# SHT_7_I_Calibration_07349-R5_L10.net
KiCad netlist of a schematic drawn in Altium Designer
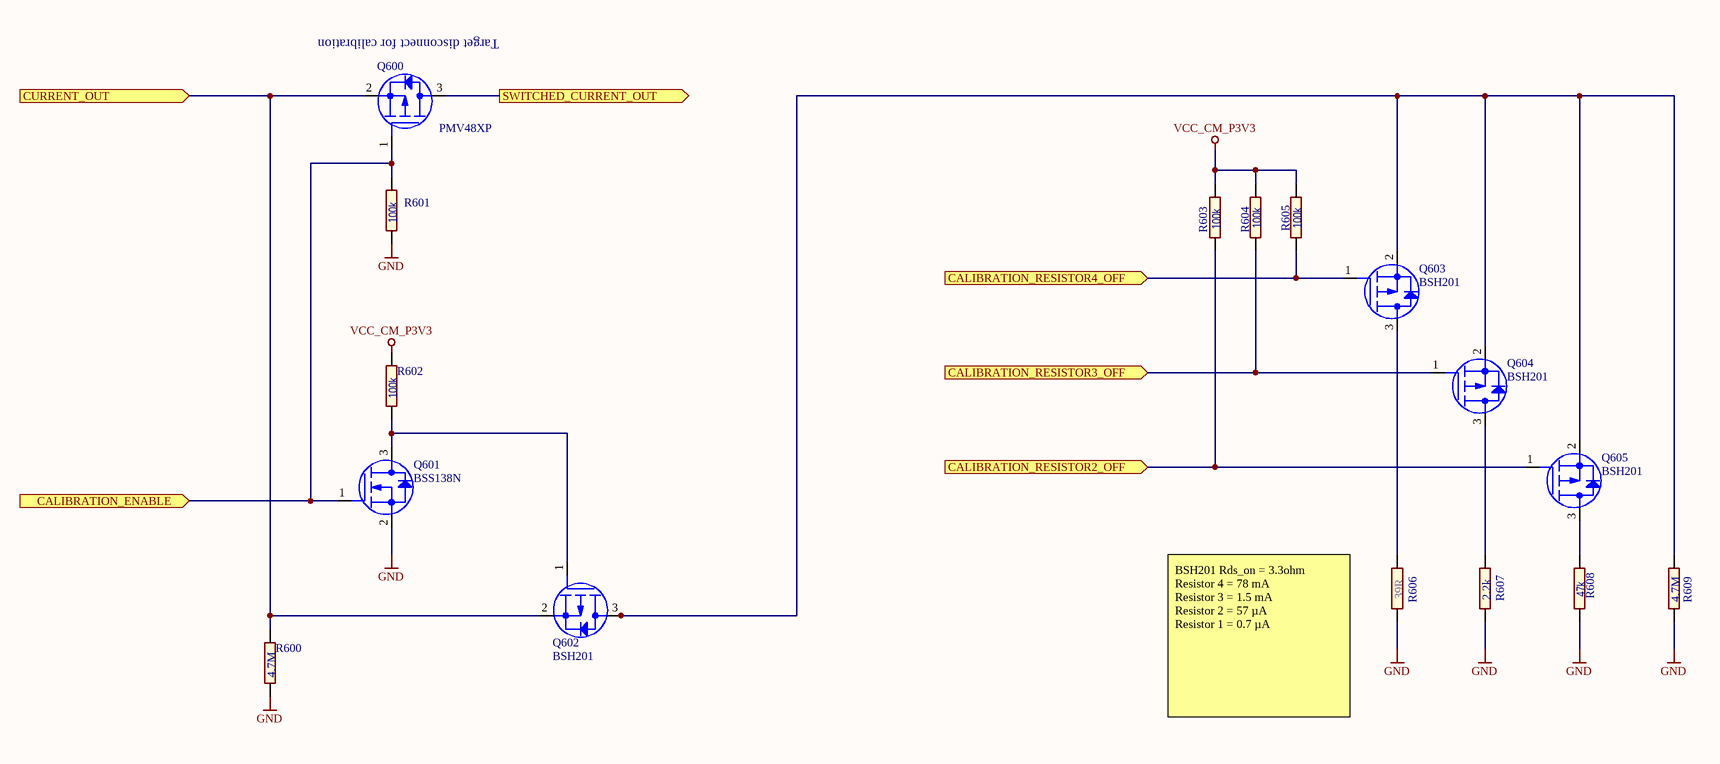
[diagram p0: SHT_7_I_Calibration_07349-R5_L10.SchDoc]

(export (version "E")
  (design (tool "Eeschema 10.0.6"))
  (components
    (comp (ref "Q600")
      (value "PMV48XP")
      (footprint "AP5-00002")
      (fields (field (name "MANUFACTURER") "NXP") (field (name "MPN") "PMV48XP,215"))
      (libsource (lib "AltiumDbLib") (part "MOSFET_P_GSD"))
    )
    (comp (ref "Q601")
      (value "BSS138N")
      (footprint "AP5-00002")
      (fields (field (name "MANUFACTURER") "Infineon"))
      (libsource (lib "AltiumDbLib") (part "MOSFET_N_GSD"))
    )
    (comp (ref "Q602")
      (value "BSH201")
      (footprint "AP5-00002")
      (fields (field (name "MANUFACTURER") "NXP") (field (name "MPN") "BSH201,215"))
      (libsource (lib "AltiumDbLib") (part "MOSFET_P_GSD"))
    )
    (comp (ref "Q603")
      (value "BSH201")
      (footprint "AP5-00002")
      (fields (field (name "MANUFACTURER") "NXP") (field (name "MPN") "BSH201,215"))
      (libsource (lib "AltiumDbLib") (part "MOSFET_P_GSD"))
    )
    (comp (ref "Q604")
      (value "BSH201")
      (footprint "AP5-00002")
      (fields (field (name "MANUFACTURER") "NXP") (field (name "MPN") "BSH201,215"))
      (libsource (lib "AltiumDbLib") (part "MOSFET_P_GSD"))
    )
    (comp (ref "Q605")
      (value "BSH201")
      (footprint "AP5-00002")
      (fields (field (name "MANUFACTURER") "NXP") (field (name "MPN") "BSH201,215"))
      (libsource (lib "AltiumDbLib") (part "MOSFET_P_GSD"))
    )
    (comp (ref "R600")
      (value "4.7M")
      (footprint "AltiumDbLib:AP2-00011")
      (description "Thick film SMD 0402 1/16W 1%")
      (fields
        (field (name "TOLERANCE") "1 %")
        (field (name "MANUFACTURER") "YAGEO CORP")
        (field (name "VERIFIED BY") "Lars Helge Mo")
      )
      (libsource (lib "AltiumDbLib") (part "R2"))
    )
    (comp (ref "R601")
      (value "100k")
      (footprint "AltiumDbLib:AP2-00011")
      (description "Thick film resistor, SMD 0402, 1/16W, 1%")
      (fields
        (field (name "TOLERANCE") "1 %")
        (field (name "MANUFACTURER") "ASJ")
        (field (name "VERIFIED BY") "Lars Helge Mo")
      )
      (libsource (lib "AltiumDbLib") (part "R2"))
    )
    (comp (ref "R602")
      (value "100k")
      (footprint "AltiumDbLib:AP2-00011")
      (description "Thick film resistor, SMD 0402, 1/16W, 1%")
      (fields
        (field (name "TOLERANCE") "1 %")
        (field (name "MANUFACTURER") "ASJ")
        (field (name "VERIFIED BY") "Lars Helge Mo")
      )
      (libsource (lib "AltiumDbLib") (part "R2"))
    )
    (comp (ref "R603")
      (value "100k")
      (footprint "AltiumDbLib:AP2-00011")
      (description "Thick film resistor, SMD 0402, 1/16W, 1%")
      (fields
        (field (name "TOLERANCE") "1 %")
        (field (name "MANUFACTURER") "ASJ")
        (field (name "VERIFIED BY") "Lars Helge Mo")
      )
      (libsource (lib "AltiumDbLib") (part "R2"))
    )
    (comp (ref "R604")
      (value "100k")
      (footprint "AltiumDbLib:AP2-00011")
      (description "Thick film resistor, SMD 0402, 1/16W, 1%")
      (fields
        (field (name "TOLERANCE") "1 %")
        (field (name "MANUFACTURER") "ASJ")
        (field (name "VERIFIED BY") "Lars Helge Mo")
      )
      (libsource (lib "AltiumDbLib") (part "R2"))
    )
    (comp (ref "R605")
      (value "100k")
      (footprint "AltiumDbLib:AP2-00011")
      (description "Thick film resistor, SMD 0402, 1/16W, 1%")
      (fields
        (field (name "TOLERANCE") "1 %")
        (field (name "MANUFACTURER") "ASJ")
        (field (name "VERIFIED BY") "Lars Helge Mo")
      )
      (libsource (lib "AltiumDbLib") (part "R2"))
    )
    (comp (ref "R606")
      (value "39R")
      (footprint "AltiumDbLib:AP2-00011")
      (description "Thick film resistor, SMD 0402, 1/16W, 1%")
      (fields
        (field (name "TOLERANCE") "1 %")
        (field (name "MPN") "CR10-39R0-FK")
        (field (name "VERIFIED BY") "Lars Helge Mo")
      )
      (libsource (lib "AltiumDbLib") (part "R2"))
    )
    (comp (ref "R607")
      (value "2.2k")
      (footprint "AltiumDbLib:AP2-00011")
      (description "Thick film resistor, SMD 0402, 1/16W, 1%")
      (fields
        (field (name "TOLERANCE") "1 %")
        (field (name "MANUFACTURER") "YAGEO CORP")
        (field (name "VERIFIED BY") "Lars Helge Mo")
      )
      (libsource (lib "AltiumDbLib") (part "R2"))
    )
    (comp (ref "R608")
      (value "47k")
      (footprint "AltiumDbLib:AP2-00011")
      (description "Thick film resistor, SMD 0402, 1/16W, 1%")
      (fields
        (field (name "TOLERANCE") "1 %")
        (field (name "MANUFACTURER") "KOA")
        (field (name "VERIFIED BY") "Lars Helge Mo")
      )
      (libsource (lib "AltiumDbLib") (part "R2"))
    )
    (comp (ref "R609")
      (value "4.7M")
      (footprint "AltiumDbLib:AP2-00011")
      (description "Thick film SMD 0402 1/16W 1%")
      (fields
        (field (name "TOLERANCE") "1 %")
        (field (name "MANUFACTURER") "YAGEO CORP")
        (field (name "VERIFIED BY") "Lars Helge Mo")
      )
      (libsource (lib "AltiumDbLib") (part "R2"))
    )
  )
  (nets
    (net (code "1") (name "/CALIBRATION_ENABLE") (class "Default")
      (node (ref "Q600") (pin "1") (pinfunction "G_1") (pintype "passive"))
      (node (ref "Q601") (pin "1") (pinfunction "G_1") (pintype "passive"))
      (node (ref "R601") (pin "2") (pinfunction "2_2") (pintype "passive"))
    )
    (net (code "2") (name "/CALIBRATION_RESISTOR2_OFF") (class "Default")
      (node (ref "Q605") (pin "1") (pinfunction "G_1") (pintype "passive"))
      (node (ref "R603") (pin "1") (pinfunction "1_1") (pintype "passive"))
    )
    (net (code "3") (name "/CALIBRATION_RESISTOR3_OFF") (class "Default")
      (node (ref "Q604") (pin "1") (pinfunction "G_1") (pintype "passive"))
      (node (ref "R604") (pin "1") (pinfunction "1_1") (pintype "passive"))
    )
    (net (code "4") (name "/CALIBRATION_RESISTOR4_OFF") (class "Default")
      (node (ref "Q603") (pin "1") (pinfunction "G_1") (pintype "passive"))
      (node (ref "R605") (pin "1") (pinfunction "1_1") (pintype "passive"))
    )
    (net (code "5") (name "/CURRENT_OUT") (class "Default")
      (node (ref "Q600") (pin "2") (pinfunction "S_2") (pintype "passive"))
      (node (ref "Q602") (pin "2") (pinfunction "S_2") (pintype "passive"))
      (node (ref "R600") (pin "2") (pinfunction "2_2") (pintype "passive"))
    )
    (net (code "6") (name "/SWITCHED_CURRENT_OUT") (class "Default")
      (node (ref "Q600") (pin "3") (pinfunction "D_3") (pintype "passive"))
    )
    (net (code "7") (name "GND") (class "Default")
      (node (ref "Q601") (pin "2") (pinfunction "S_2") (pintype "passive"))
      (node (ref "R600") (pin "1") (pinfunction "1_1") (pintype "passive"))
      (node (ref "R601") (pin "1") (pinfunction "1_1") (pintype "passive"))
      (node (ref "R606") (pin "1") (pinfunction "1_1") (pintype "passive"))
      (node (ref "R607") (pin "1") (pinfunction "1_1") (pintype "passive"))
      (node (ref "R608") (pin "1") (pinfunction "1_1") (pintype "passive"))
      (node (ref "R609") (pin "1") (pinfunction "1_1") (pintype "passive"))
    )
    (net (code "8") (name "Net-(Q601-D)") (class "Default")
      (node (ref "Q601") (pin "3") (pinfunction "D_3") (pintype "passive"))
      (node (ref "Q602") (pin "1") (pinfunction "G_1") (pintype "passive"))
      (node (ref "R602") (pin "1") (pinfunction "1_1") (pintype "passive"))
    )
    (net (code "9") (name "Net-(Q602-D)") (class "Default")
      (node (ref "Q602") (pin "3") (pinfunction "D_3") (pintype "passive"))
      (node (ref "Q603") (pin "2") (pinfunction "S_2") (pintype "passive"))
      (node (ref "Q604") (pin "2") (pinfunction "S_2") (pintype "passive"))
      (node (ref "Q605") (pin "2") (pinfunction "S_2") (pintype "passive"))
      (node (ref "R609") (pin "2") (pinfunction "2_2") (pintype "passive"))
    )
    (net (code "10") (name "Net-(Q603-D)") (class "Default")
      (node (ref "Q603") (pin "3") (pinfunction "D_3") (pintype "passive"))
      (node (ref "R606") (pin "2") (pinfunction "2_2") (pintype "passive"))
    )
    (net (code "11") (name "Net-(Q604-D)") (class "Default")
      (node (ref "Q604") (pin "3") (pinfunction "D_3") (pintype "passive"))
      (node (ref "R607") (pin "2") (pinfunction "2_2") (pintype "passive"))
    )
    (net (code "12") (name "Net-(Q605-D)") (class "Default")
      (node (ref "Q605") (pin "3") (pinfunction "D_3") (pintype "passive"))
      (node (ref "R608") (pin "2") (pinfunction "2_2") (pintype "passive"))
    )
    (net (code "13") (name "VCC_CM_P3V3") (class "Default")
      (node (ref "R602") (pin "2") (pinfunction "2_2") (pintype "passive"))
      (node (ref "R603") (pin "2") (pinfunction "2_2") (pintype "passive"))
      (node (ref "R604") (pin "2") (pinfunction "2_2") (pintype "passive"))
      (node (ref "R605") (pin "2") (pinfunction "2_2") (pintype "passive"))
    )
  )
)
